# 477breakout2.net
KiCad netlist of a schematic drawn in EAGLE
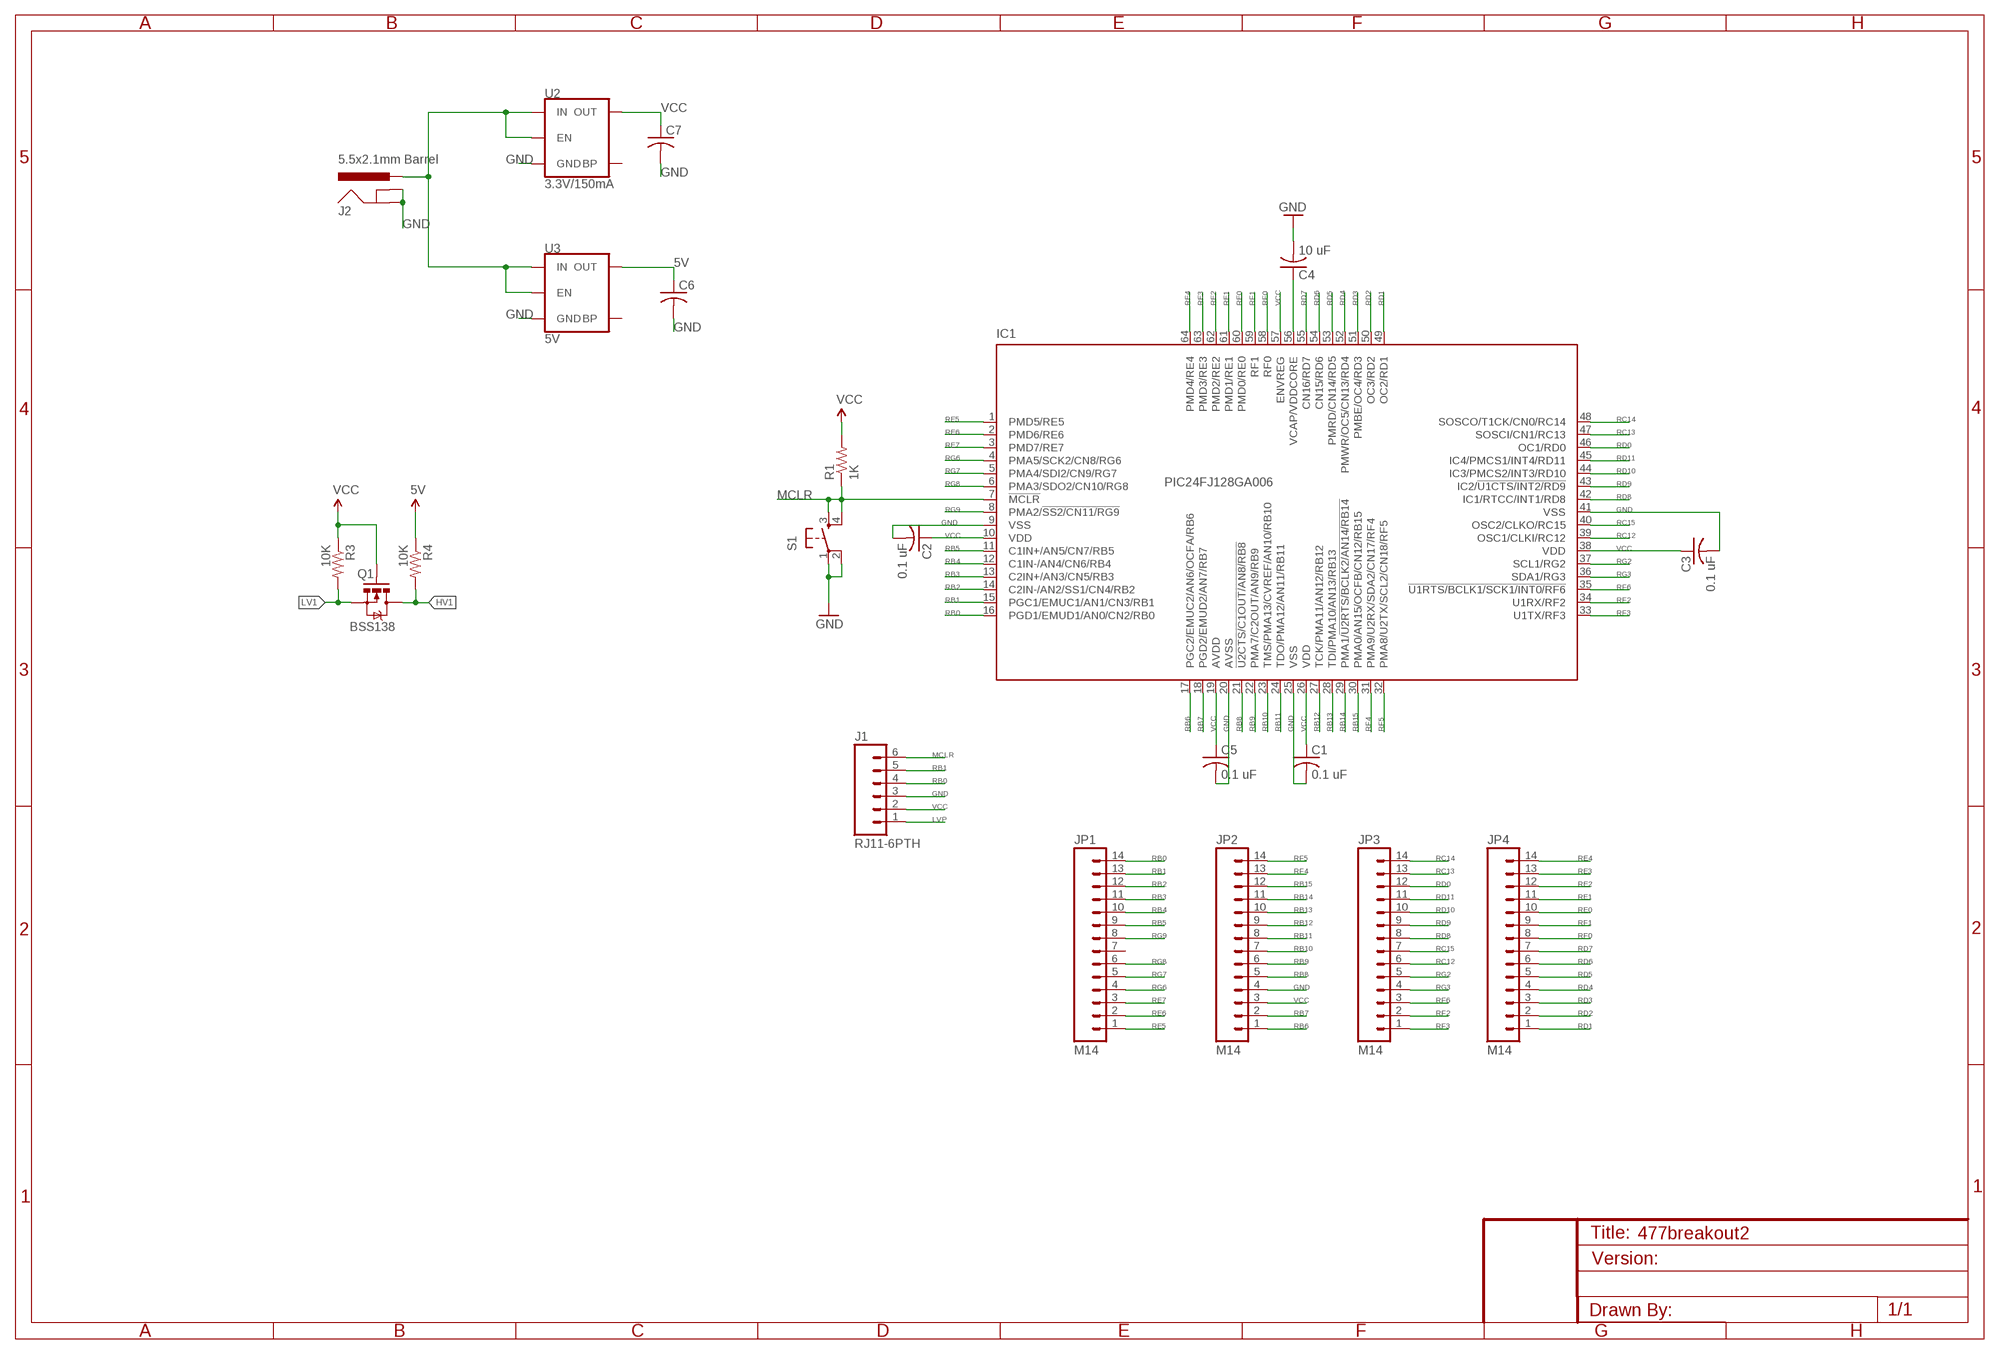
[diagram p0: schematic, sheet 1]

(export (version "E")
  (design (tool "Eeschema 10.0.6"))
  (components
    (comp (ref "C1")
      (value "0.1 uF")
      (footprint "eagle-import:C0402")
      (libsource (lib "eagle-import") (part "C-USC0402"))
    )
    (comp (ref "C2")
      (value "0.1 uF")
      (footprint "eagle-import:C0402")
      (libsource (lib "eagle-import") (part "C-USC0402"))
    )
    (comp (ref "C3")
      (value "0.1 uF")
      (footprint "eagle-import:C0402")
      (libsource (lib "eagle-import") (part "C-USC0402"))
    )
    (comp (ref "C4")
      (value "10 uF")
      (footprint "eagle-import:C0805")
      (libsource (lib "eagle-import") (part "C-USC0805"))
    )
    (comp (ref "C5")
      (value "0.1 uF")
      (footprint "eagle-import:C0402")
      (libsource (lib "eagle-import") (part "C-USC0402"))
    )
    (comp (ref "C6")
      (value "C-USC1206")
      (footprint "eagle-import:C1206")
      (libsource (lib "eagle-import") (part "C-USC1206"))
    )
    (comp (ref "C7")
      (value "C-USC1206")
      (footprint "eagle-import:C1206")
      (libsource (lib "eagle-import") (part "C-USC1206"))
    )
    (comp (ref "IC1")
      (value "PIC24FJ128GA006")
      (footprint "eagle-import:TQFP64-10X10")
      (fields (field (name "MF") "MICROCHIP") (field (name "MPN") "PIC24FJ128GA006-I/PT"))
      (libsource (lib "eagle-import") (part "PIC24FJGA006128"))
    )
    (comp (ref "J1")
      (value "RJ11-6PTH")
      (footprint "eagle-import:RJ11-6")
      (libsource (lib "eagle-import") (part "RJ11-6PTH"))
    )
    (comp (ref "J2")
      (value "5.5x2.1mm Barrel")
      (footprint "eagle-import:POWER_JACK_SMD")
      (libsource (lib "eagle-import") (part "POWER_JACKSMD"))
    )
    (comp (ref "JP1")
      (value "M14")
      (footprint "eagle-import:1X14")
      (libsource (lib "eagle-import") (part "M14"))
    )
    (comp (ref "JP2")
      (value "M14")
      (footprint "eagle-import:1X14")
      (libsource (lib "eagle-import") (part "M14"))
    )
    (comp (ref "JP3")
      (value "M14")
      (footprint "eagle-import:1X14")
      (libsource (lib "eagle-import") (part "M14"))
    )
    (comp (ref "JP4")
      (value "M14")
      (footprint "eagle-import:1X14")
      (libsource (lib "eagle-import") (part "M14"))
    )
    (comp (ref "Q1")
      (value "BSS138")
      (footprint "eagle-import:SOT23-3")
      (libsource (lib "eagle-import") (part "MOSFET-NCHANNELSMD"))
    )
    (comp (ref "R1")
      (value "1K")
      (footprint "eagle-import:0204_7")
      (libsource (lib "eagle-import") (part "R-US_0204/7"))
    )
    (comp (ref "R3")
      (value "10K")
      (footprint "eagle-import:0603-RES")
      (libsource (lib "eagle-import") (part "RESISTOR0603-RES"))
    )
    (comp (ref "R4")
      (value "10K")
      (footprint "eagle-import:0603-RES")
      (libsource (lib "eagle-import") (part "RESISTOR0603-RES"))
    )
    (comp (ref "S1")
      (value "TAC_SWITCHPTH")
      (footprint "eagle-import:TACTILE-PTH")
      (libsource (lib "eagle-import") (part "TAC_SWITCHPTH"))
    )
    (comp (ref "U2")
      (value "3.3V/150mA")
      (footprint "eagle-import:SOT23-5")
      (libsource (lib "eagle-import") (part "V_REG_MIC52053.3V"))
    )
    (comp (ref "U3")
      (value "5V")
      (footprint "eagle-import:SOT23-5")
      (libsource (lib "eagle-import") (part "V_REG_MIC52055V"))
    )
  )
  (nets
    (net (code "1") (name "/LVP") (class "Default")
      (node (ref "J1") (pin "1") (pinfunction "1_1") (pintype "passive"))
    )
    (net (code "2") (name "/MCLR") (class "Default")
      (node (ref "IC1") (pin "7") (pinfunction "~{MCLR}_7") (pintype "bidirectional"))
      (node (ref "J1") (pin "6") (pinfunction "6_6") (pintype "passive"))
      (node (ref "R1") (pin "1") (pinfunction "1_1") (pintype "passive"))
      (node (ref "S1") (pin "3") (pinfunction "3_3") (pintype "passive"))
      (node (ref "S1") (pin "4") (pinfunction "4_4") (pintype "passive"))
    )
    (net (code "3") (name "/RB0") (class "Default")
      (node (ref "IC1") (pin "16") (pinfunction "PGD1/EMUD1/AN0/CN2/RB0_16") (pintype "bidirectional"))
      (node (ref "J1") (pin "4") (pinfunction "4_4") (pintype "passive"))
      (node (ref "JP1") (pin "14") (pinfunction "14_14") (pintype "passive"))
    )
    (net (code "4") (name "/RB1") (class "Default")
      (node (ref "IC1") (pin "15") (pinfunction "PGC1/EMUC1/AN1/CN3/RB1_15") (pintype "bidirectional"))
      (node (ref "J1") (pin "5") (pinfunction "5_5") (pintype "passive"))
      (node (ref "JP1") (pin "13") (pinfunction "13_13") (pintype "passive"))
    )
    (net (code "5") (name "/RB2") (class "Default")
      (node (ref "IC1") (pin "14") (pinfunction "C2IN-/AN2/SS1/CN4/RB2_14") (pintype "bidirectional"))
      (node (ref "JP1") (pin "12") (pinfunction "12_12") (pintype "passive"))
    )
    (net (code "6") (name "/RB3") (class "Default")
      (node (ref "IC1") (pin "13") (pinfunction "C2IN+/AN3/CN5/RB3_13") (pintype "bidirectional"))
      (node (ref "JP1") (pin "11") (pinfunction "11_11") (pintype "passive"))
    )
    (net (code "7") (name "/RB4") (class "Default")
      (node (ref "IC1") (pin "12") (pinfunction "C1IN-/AN4/CN6/RB4_12") (pintype "bidirectional"))
      (node (ref "JP1") (pin "10") (pinfunction "10_10") (pintype "passive"))
    )
    (net (code "8") (name "/RB5") (class "Default")
      (node (ref "IC1") (pin "11") (pinfunction "C1IN+/AN5/CN7/RB5_11") (pintype "bidirectional"))
      (node (ref "JP1") (pin "9") (pinfunction "9_9") (pintype "passive"))
    )
    (net (code "9") (name "/RB6") (class "Default")
      (node (ref "IC1") (pin "17") (pinfunction "PGC2/EMUC2/AN6/OCFA/RB6_17") (pintype "bidirectional"))
      (node (ref "JP2") (pin "1") (pinfunction "1_1") (pintype "passive"))
    )
    (net (code "10") (name "/RB7") (class "Default")
      (node (ref "IC1") (pin "18") (pinfunction "PGD2/EMUD2/AN7/RB7_18") (pintype "bidirectional"))
      (node (ref "JP2") (pin "2") (pinfunction "2_2") (pintype "passive"))
    )
    (net (code "11") (name "/RB8") (class "Default")
      (node (ref "IC1") (pin "21") (pinfunction "~{U2CTS/C1OUT/AN8/RB8}_21") (pintype "bidirectional"))
      (node (ref "JP2") (pin "5") (pinfunction "5_5") (pintype "passive"))
    )
    (net (code "12") (name "/RB9") (class "Default")
      (node (ref "IC1") (pin "22") (pinfunction "PMA7/C2OUT/AN9/RB9_22") (pintype "bidirectional"))
      (node (ref "JP2") (pin "6") (pinfunction "6_6") (pintype "passive"))
    )
    (net (code "13") (name "/RB10") (class "Default")
      (node (ref "IC1") (pin "23") (pinfunction "TMS/PMA13/CVREF/AN10/RB10_23") (pintype "bidirectional"))
      (node (ref "JP2") (pin "7") (pinfunction "7_7") (pintype "passive"))
    )
    (net (code "14") (name "/RB11") (class "Default")
      (node (ref "IC1") (pin "24") (pinfunction "TDO/PMA12/AN11/RB11_24") (pintype "bidirectional"))
      (node (ref "JP2") (pin "8") (pinfunction "8_8") (pintype "passive"))
    )
    (net (code "15") (name "/RB12") (class "Default")
      (node (ref "IC1") (pin "27") (pinfunction "TCK/PMA11/AN12/RB12_27") (pintype "bidirectional"))
      (node (ref "JP2") (pin "9") (pinfunction "9_9") (pintype "passive"))
    )
    (net (code "16") (name "/RB13") (class "Default")
      (node (ref "IC1") (pin "28") (pinfunction "TDI/PMA10/AN13/RB13_28") (pintype "bidirectional"))
      (node (ref "JP2") (pin "10") (pinfunction "10_10") (pintype "passive"))
    )
    (net (code "17") (name "/RB14") (class "Default")
      (node (ref "IC1") (pin "29") (pinfunction "PMA1/~{U2RTS/BCLK2/AN14/RB14}_29") (pintype "bidirectional"))
      (node (ref "JP2") (pin "11") (pinfunction "11_11") (pintype "passive"))
    )
    (net (code "18") (name "/RB15") (class "Default")
      (node (ref "IC1") (pin "30") (pinfunction "PMA0/AN15/OCFB/CN12/RB15_30") (pintype "bidirectional"))
      (node (ref "JP2") (pin "12") (pinfunction "12_12") (pintype "passive"))
    )
    (net (code "19") (name "/RC12") (class "Default")
      (node (ref "IC1") (pin "39") (pinfunction "OSC1/CLKI/RC12_39") (pintype "bidirectional"))
      (node (ref "JP3") (pin "6") (pinfunction "6_6") (pintype "passive"))
    )
    (net (code "20") (name "/RC13") (class "Default")
      (node (ref "IC1") (pin "47") (pinfunction "SOSCI/CN1/RC13_47") (pintype "bidirectional"))
      (node (ref "JP3") (pin "13") (pinfunction "13_13") (pintype "passive"))
    )
    (net (code "21") (name "/RC14") (class "Default")
      (node (ref "IC1") (pin "48") (pinfunction "SOSCO/T1CK/CN0/RC14_48") (pintype "bidirectional"))
      (node (ref "JP3") (pin "14") (pinfunction "14_14") (pintype "passive"))
    )
    (net (code "22") (name "/RC15") (class "Default")
      (node (ref "IC1") (pin "40") (pinfunction "OSC2/CLKO/RC15_40") (pintype "bidirectional"))
      (node (ref "JP3") (pin "7") (pinfunction "7_7") (pintype "passive"))
    )
    (net (code "23") (name "/RD0") (class "Default")
      (node (ref "IC1") (pin "46") (pinfunction "OC1/RD0_46") (pintype "bidirectional"))
      (node (ref "JP3") (pin "12") (pinfunction "12_12") (pintype "passive"))
    )
    (net (code "24") (name "/RD1") (class "Default")
      (node (ref "IC1") (pin "49") (pinfunction "OC2/RD1_49") (pintype "bidirectional"))
      (node (ref "JP4") (pin "1") (pinfunction "1_1") (pintype "passive"))
    )
    (net (code "25") (name "/RD2") (class "Default")
      (node (ref "IC1") (pin "50") (pinfunction "OC3/RD2_50") (pintype "bidirectional"))
      (node (ref "JP4") (pin "2") (pinfunction "2_2") (pintype "passive"))
    )
    (net (code "26") (name "/RD3") (class "Default")
      (node (ref "IC1") (pin "51") (pinfunction "PMBE/OC4/RD3_51") (pintype "bidirectional"))
      (node (ref "JP4") (pin "3") (pinfunction "3_3") (pintype "passive"))
    )
    (net (code "27") (name "/RD4") (class "Default")
      (node (ref "IC1") (pin "52") (pinfunction "PMWR/OC5/CN13/RD4_52") (pintype "bidirectional"))
      (node (ref "JP4") (pin "4") (pinfunction "4_4") (pintype "passive"))
    )
    (net (code "28") (name "/RD5") (class "Default")
      (node (ref "IC1") (pin "53") (pinfunction "PMRD/CN14/RD5_53") (pintype "bidirectional"))
      (node (ref "JP4") (pin "5") (pinfunction "5_5") (pintype "passive"))
    )
    (net (code "29") (name "/RD6") (class "Default")
      (node (ref "IC1") (pin "54") (pinfunction "CN15/RD6_54") (pintype "bidirectional"))
      (node (ref "JP4") (pin "6") (pinfunction "6_6") (pintype "passive"))
    )
    (net (code "30") (name "/RD7") (class "Default")
      (node (ref "IC1") (pin "55") (pinfunction "CN16/RD7_55") (pintype "bidirectional"))
      (node (ref "JP4") (pin "7") (pinfunction "7_7") (pintype "passive"))
    )
    (net (code "31") (name "/RD8") (class "Default")
      (node (ref "IC1") (pin "42") (pinfunction "IC1/RTCC/INT1/RD8_42") (pintype "bidirectional"))
      (node (ref "JP3") (pin "8") (pinfunction "8_8") (pintype "passive"))
    )
    (net (code "32") (name "/RD9") (class "Default")
      (node (ref "IC1") (pin "43") (pinfunction "IC2/~{U1CTS/INT2/RD9}_43") (pintype "bidirectional"))
      (node (ref "JP3") (pin "9") (pinfunction "9_9") (pintype "passive"))
    )
    (net (code "33") (name "/RD10") (class "Default")
      (node (ref "IC1") (pin "44") (pinfunction "IC3/PMCS2/INT3/RD10_44") (pintype "bidirectional"))
      (node (ref "JP3") (pin "10") (pinfunction "10_10") (pintype "passive"))
    )
    (net (code "34") (name "/RD11") (class "Default")
      (node (ref "IC1") (pin "45") (pinfunction "IC4/PMCS1/INT4/RD11_45") (pintype "bidirectional"))
      (node (ref "JP3") (pin "11") (pinfunction "11_11") (pintype "passive"))
    )
    (net (code "35") (name "/RE0") (class "Default")
      (node (ref "IC1") (pin "60") (pinfunction "PMD0/RE0_60") (pintype "bidirectional"))
      (node (ref "JP4") (pin "10") (pinfunction "10_10") (pintype "passive"))
    )
    (net (code "36") (name "/RE1") (class "Default")
      (node (ref "IC1") (pin "61") (pinfunction "PMD1/RE1_61") (pintype "bidirectional"))
      (node (ref "JP4") (pin "11") (pinfunction "11_11") (pintype "passive"))
    )
    (net (code "37") (name "/RE2") (class "Default")
      (node (ref "IC1") (pin "62") (pinfunction "PMD2/RE2_62") (pintype "bidirectional"))
      (node (ref "JP4") (pin "12") (pinfunction "12_12") (pintype "passive"))
    )
    (net (code "38") (name "/RE3") (class "Default")
      (node (ref "IC1") (pin "63") (pinfunction "PMD3/RE3_63") (pintype "bidirectional"))
      (node (ref "JP4") (pin "13") (pinfunction "13_13") (pintype "passive"))
    )
    (net (code "39") (name "/RE4") (class "Default")
      (node (ref "IC1") (pin "64") (pinfunction "PMD4/RE4_64") (pintype "bidirectional"))
      (node (ref "JP4") (pin "14") (pinfunction "14_14") (pintype "passive"))
    )
    (net (code "40") (name "/RE5") (class "Default")
      (node (ref "IC1") (pin "1") (pinfunction "PMD5/RE5_1") (pintype "bidirectional"))
      (node (ref "JP1") (pin "1") (pinfunction "1_1") (pintype "passive"))
    )
    (net (code "41") (name "/RE6") (class "Default")
      (node (ref "IC1") (pin "2") (pinfunction "PMD6/RE6_2") (pintype "bidirectional"))
      (node (ref "JP1") (pin "2") (pinfunction "2_2") (pintype "passive"))
    )
    (net (code "42") (name "/RE7") (class "Default")
      (node (ref "IC1") (pin "3") (pinfunction "PMD7/RE7_3") (pintype "bidirectional"))
      (node (ref "JP1") (pin "3") (pinfunction "3_3") (pintype "passive"))
    )
    (net (code "43") (name "/RF0") (class "Default")
      (node (ref "IC1") (pin "58") (pinfunction "RF0_58") (pintype "bidirectional"))
      (node (ref "JP4") (pin "8") (pinfunction "8_8") (pintype "passive"))
    )
    (net (code "44") (name "/RF1") (class "Default")
      (node (ref "IC1") (pin "59") (pinfunction "RF1_59") (pintype "bidirectional"))
      (node (ref "JP4") (pin "9") (pinfunction "9_9") (pintype "passive"))
    )
    (net (code "45") (name "/RF2") (class "Default")
      (node (ref "IC1") (pin "34") (pinfunction "U1RX/RF2_34") (pintype "bidirectional"))
      (node (ref "JP3") (pin "2") (pinfunction "2_2") (pintype "passive"))
    )
    (net (code "46") (name "/RF3") (class "Default")
      (node (ref "IC1") (pin "33") (pinfunction "U1TX/RF3_33") (pintype "bidirectional"))
      (node (ref "JP3") (pin "1") (pinfunction "1_1") (pintype "passive"))
    )
    (net (code "47") (name "/RF4") (class "Default")
      (node (ref "IC1") (pin "31") (pinfunction "PMA9/U2RX/SDA2/CN17/RF4_31") (pintype "bidirectional"))
      (node (ref "JP2") (pin "13") (pinfunction "13_13") (pintype "passive"))
    )
    (net (code "48") (name "/RF5") (class "Default")
      (node (ref "IC1") (pin "32") (pinfunction "PMA8/U2TX/SCL2/CN18/RF5_32") (pintype "bidirectional"))
      (node (ref "JP2") (pin "14") (pinfunction "14_14") (pintype "passive"))
    )
    (net (code "49") (name "/RF6") (class "Default")
      (node (ref "IC1") (pin "35") (pinfunction "~{U1RTS/BCLK1/SCK1/INT0/RF6}_35") (pintype "bidirectional"))
      (node (ref "JP3") (pin "3") (pinfunction "3_3") (pintype "passive"))
    )
    (net (code "50") (name "/RG2") (class "Default")
      (node (ref "IC1") (pin "37") (pinfunction "SCL1/RG2_37") (pintype "bidirectional"))
      (node (ref "JP3") (pin "5") (pinfunction "5_5") (pintype "passive"))
    )
    (net (code "51") (name "/RG3") (class "Default")
      (node (ref "IC1") (pin "36") (pinfunction "SDA1/RG3_36") (pintype "bidirectional"))
      (node (ref "JP3") (pin "4") (pinfunction "4_4") (pintype "passive"))
    )
    (net (code "52") (name "/RG6") (class "Default")
      (node (ref "IC1") (pin "4") (pinfunction "PMA5/SCK2/CN8/RG6_4") (pintype "bidirectional"))
      (node (ref "JP1") (pin "4") (pinfunction "4_4") (pintype "passive"))
    )
    (net (code "53") (name "/RG7") (class "Default")
      (node (ref "IC1") (pin "5") (pinfunction "PMA4/SDI2/CN9/RG7_5") (pintype "bidirectional"))
      (node (ref "JP1") (pin "5") (pinfunction "5_5") (pintype "passive"))
    )
    (net (code "54") (name "/RG8") (class "Default")
      (node (ref "IC1") (pin "6") (pinfunction "PMA3/SDO2/CN10/RG8_6") (pintype "bidirectional"))
      (node (ref "JP1") (pin "6") (pinfunction "6_6") (pintype "passive"))
    )
    (net (code "55") (name "/RG9") (class "Default")
      (node (ref "IC1") (pin "8") (pinfunction "PMA2/~{SS2/CN11/RG9}_8") (pintype "bidirectional"))
      (node (ref "JP1") (pin "8") (pinfunction "8_8") (pintype "passive"))
    )
    (net (code "56") (name "5V") (class "Default")
      (node (ref "C6") (pin "1") (pinfunction "1_1") (pintype "passive"))
      (node (ref "R4") (pin "1") (pinfunction "1_1") (pintype "passive"))
      (node (ref "U3") (pin "5") (pinfunction "OUT_5") (pintype "passive"))
    )
    (net (code "57") (name "GND") (class "Default")
      (node (ref "C1") (pin "2") (pinfunction "2_2") (pintype "passive"))
      (node (ref "C2") (pin "2") (pinfunction "2_2") (pintype "passive"))
      (node (ref "C3") (pin "2") (pinfunction "2_2") (pintype "passive"))
      (node (ref "C4") (pin "2") (pinfunction "2_2") (pintype "passive"))
      (node (ref "C5") (pin "2") (pinfunction "2_2") (pintype "passive"))
      (node (ref "C6") (pin "2") (pinfunction "2_2") (pintype "passive"))
      (node (ref "C7") (pin "2") (pinfunction "2_2") (pintype "passive"))
      (node (ref "IC1") (pin "20") (pinfunction "AVSS_20") (pintype "power_in"))
      (node (ref "IC1") (pin "25") (pinfunction "VSS_25") (pintype "power_in"))
      (node (ref "IC1") (pin "41") (pinfunction "VSS_41") (pintype "power_in"))
      (node (ref "IC1") (pin "9") (pinfunction "VSS_9") (pintype "power_in"))
      (node (ref "J1") (pin "3") (pinfunction "3_3") (pintype "passive"))
      (node (ref "J2") (pin "GND") (pinfunction "GNDBREAK_GND") (pintype "bidirectional"))
      (node (ref "J2") (pin "P$4") (pinfunction "GND_P$4") (pintype "bidirectional"))
      (node (ref "JP2") (pin "4") (pinfunction "4_4") (pintype "passive"))
      (node (ref "S1") (pin "1") (pinfunction "1_1") (pintype "passive"))
      (node (ref "S1") (pin "2") (pinfunction "2_2") (pintype "passive"))
      (node (ref "U2") (pin "2") (pinfunction "GND_2") (pintype "input"))
      (node (ref "U3") (pin "2") (pinfunction "GND_2") (pintype "input"))
    )
    (net (code "58") (name "HV1") (class "Default")
      (node (ref "Q1") (pin "3") (pinfunction "D_3") (pintype "passive"))
      (node (ref "R4") (pin "2") (pinfunction "2_2") (pintype "passive"))
    )
    (net (code "59") (name "LV1") (class "Default")
      (node (ref "Q1") (pin "2") (pinfunction "S_2") (pintype "passive"))
      (node (ref "R3") (pin "2") (pinfunction "2_2") (pintype "passive"))
    )
    (net (code "60") (name "Net-(IC1-VCAP{slash}VDDCORE)") (class "Default")
      (node (ref "C4") (pin "1") (pinfunction "1_1") (pintype "passive"))
      (node (ref "IC1") (pin "56") (pinfunction "VCAP/VDDCORE_56") (pintype "bidirectional"))
    )
    (net (code "61") (name "Net-(J2-PWR)") (class "Default")
      (node (ref "J2") (pin "VIN0") (pinfunction "PWR_VIN0") (pintype "bidirectional"))
      (node (ref "U2") (pin "1") (pinfunction "IN_1") (pintype "input"))
      (node (ref "U2") (pin "3") (pinfunction "EN_3") (pintype "input"))
      (node (ref "U3") (pin "1") (pinfunction "IN_1") (pintype "input"))
      (node (ref "U3") (pin "3") (pinfunction "EN_3") (pintype "input"))
    )
    (net (code "62") (name "VCC") (class "Default")
      (node (ref "C1") (pin "1") (pinfunction "1_1") (pintype "passive"))
      (node (ref "C2") (pin "1") (pinfunction "1_1") (pintype "passive"))
      (node (ref "C3") (pin "1") (pinfunction "1_1") (pintype "passive"))
      (node (ref "C5") (pin "1") (pinfunction "1_1") (pintype "passive"))
      (node (ref "C7") (pin "1") (pinfunction "1_1") (pintype "passive"))
      (node (ref "IC1") (pin "10") (pinfunction "VDD_10") (pintype "power_in"))
      (node (ref "IC1") (pin "19") (pinfunction "AVDD_19") (pintype "power_in"))
      (node (ref "IC1") (pin "26") (pinfunction "VDD_26") (pintype "power_in"))
      (node (ref "IC1") (pin "38") (pinfunction "VDD_38") (pintype "power_in"))
      (node (ref "IC1") (pin "57") (pinfunction "ENVREG_57") (pintype "bidirectional"))
      (node (ref "J1") (pin "2") (pinfunction "2_2") (pintype "passive"))
      (node (ref "JP2") (pin "3") (pinfunction "3_3") (pintype "passive"))
      (node (ref "Q1") (pin "1") (pinfunction "G_1") (pintype "passive"))
      (node (ref "R1") (pin "2") (pinfunction "2_2") (pintype "passive"))
      (node (ref "R3") (pin "1") (pinfunction "1_1") (pintype "passive"))
      (node (ref "U2") (pin "5") (pinfunction "OUT_5") (pintype "passive"))
    )
    (net (code "63") (name "unconnected-(JP1-Pad7)") (class "Default")
      (node (ref "JP1") (pin "7") (pinfunction "7_7") (pintype "passive"))
    )
    (net (code "64") (name "unconnected-(U2-BP-Pad4)") (class "Default")
      (node (ref "U2") (pin "4") (pinfunction "BP_4") (pintype "input"))
    )
    (net (code "65") (name "unconnected-(U3-BP-Pad4)") (class "Default")
      (node (ref "U3") (pin "4") (pinfunction "BP_4") (pintype "input"))
    )
  )
)
